# Due_Breakout_Board_Headers.net
KiCad netlist of a schematic drawn in Altium Designer
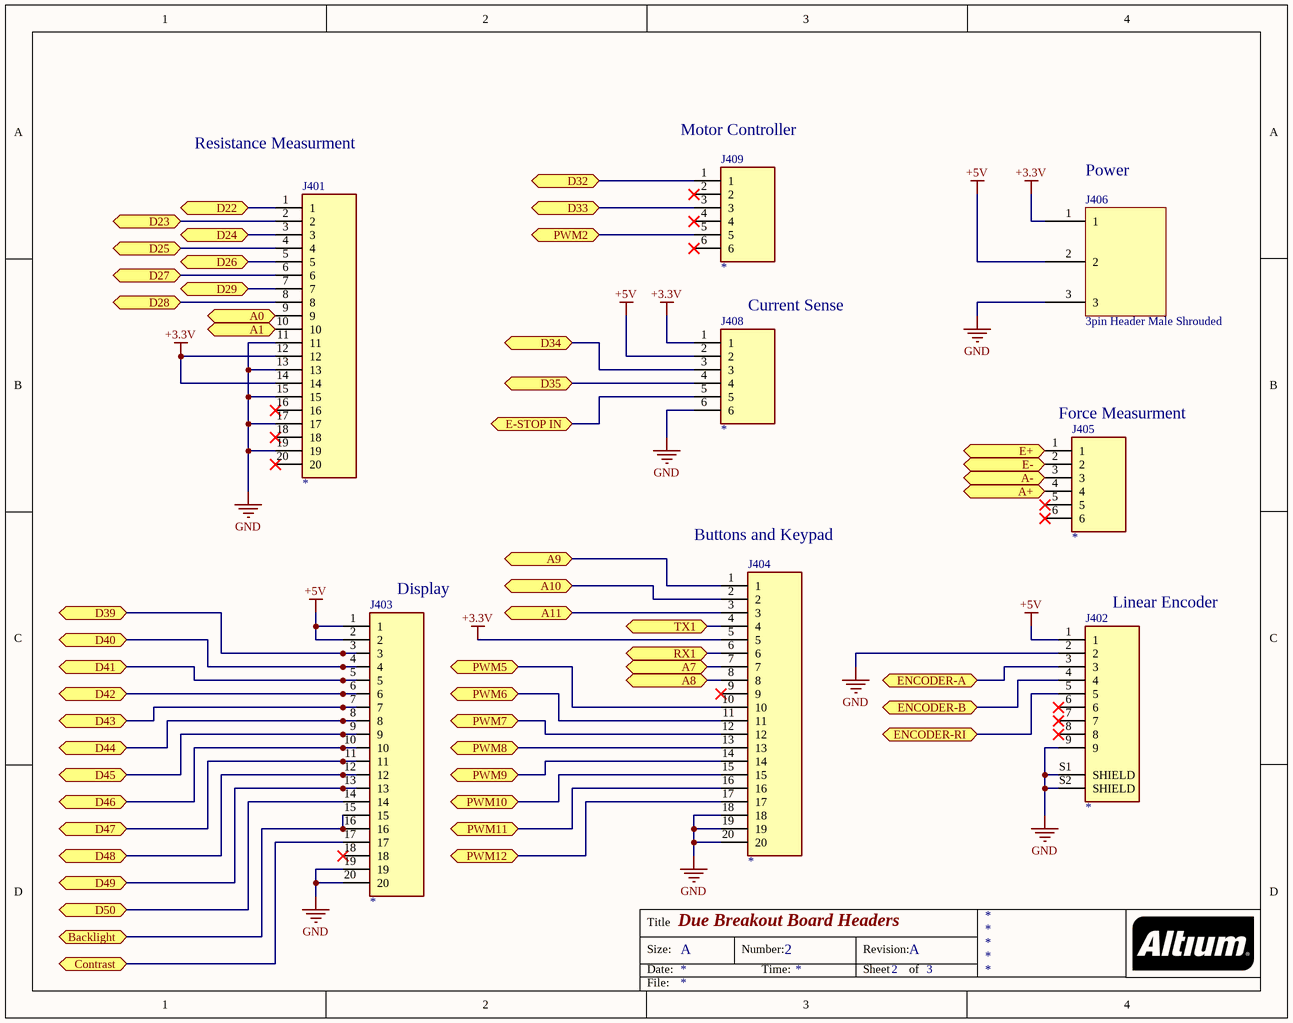
[diagram p0: Due_Breakout_Board Headers.SchDoc]

(export (version "E")
  (design (tool "Eeschema 10.0.6"))
  (components
    (comp (ref "J401")
      (value "*")
      (footprint "TE_1761681-7")
      (description "IDC LOW PRO HDR 50P VERT HT BLACK")
      (fields (field (name "MP") "1761681-7"))
      (libsource (lib "1761681-7") (part "1761681-7"))
    )
    (comp (ref "J402")
      (value "1-5747150-6")
      (footprint "TE_1-5747150-6")
      (description "9 Position D-Sub Receptacle, Female Sockets Connector")
      (fields (field (name "MF") "TE Connectivity") (field (name "COMMENT_1") "*"))
      (libsource (lib "1-5747150-6") (part "1-5747150-6"))
    )
    (comp (ref "J403")
      (value "*")
      (footprint "TE_1761681-7")
      (description "IDC LOW PRO HDR 50P VERT HT BLACK")
      (fields (field (name "MP") "1761681-7"))
      (libsource (lib "1761681-7") (part "1761681-7"))
    )
    (comp (ref "J404")
      (value "*")
      (footprint "TE_1761681-7")
      (description "IDC LOW PRO HDR 50P VERT HT BLACK")
      (fields (field (name "MP") "1761681-7"))
      (libsource (lib "1761681-7") (part "1761681-7"))
    )
    (comp (ref "J405")
      (value "*")
      (footprint "TE_1761681-1")
      (fields (field (name "MP") "1761681-1") (field (name "MF") "{'manufacturer': 'TE Connectivity'}"))
      (libsource (lib "1761681-1") (part "1761681-1"))
    )
    (comp (ref "J406")
      (value "3pin Header Male Shrouded")
      (footprint "3Pin Header")
      (libsource (lib "Components") (part "3pin Header Male Shrouded"))
    )
    (comp (ref "J408")
      (value "*")
      (footprint "TE_1761681-1")
      (fields (field (name "MP") "1761681-1") (field (name "MF") "{'manufacturer': 'TE Connectivity'}"))
      (libsource (lib "1761681-1") (part "1761681-1"))
    )
    (comp (ref "J409")
      (value "*")
      (footprint "TE_1761681-1")
      (fields (field (name "MP") "1761681-1") (field (name "MF") "{'manufacturer': 'TE Connectivity'}"))
      (libsource (lib "1761681-1") (part "1761681-1"))
    )
  )
  (nets
    (net (code "1") (name "+3.3V") (class "Default")
      (node (ref "J401") (pin "12") (pinfunction "12_12") (pintype "passive"))
      (node (ref "J401") (pin "14") (pinfunction "14_14") (pintype "passive"))
      (node (ref "J404") (pin "5") (pinfunction "5_5") (pintype "passive"))
      (node (ref "J406") (pin "1") (pinfunction "1_1") (pintype "passive"))
      (node (ref "J408") (pin "1") (pinfunction "1_1") (pintype "passive"))
    )
    (net (code "2") (name "+5V") (class "Default")
      (node (ref "J402") (pin "1") (pinfunction "1_1") (pintype "passive"))
      (node (ref "J403") (pin "1") (pinfunction "1_1") (pintype "passive"))
      (node (ref "J403") (pin "2") (pinfunction "2_2") (pintype "passive"))
      (node (ref "J406") (pin "2") (pinfunction "2_2") (pintype "passive"))
      (node (ref "J408") (pin "2") (pinfunction "2_2") (pintype "passive"))
    )
    (net (code "3") (name "/A+") (class "Default")
      (node (ref "J405") (pin "4") (pinfunction "4_4") (pintype "passive"))
    )
    (net (code "4") (name "/A-") (class "Default")
      (node (ref "J405") (pin "3") (pinfunction "3_3") (pintype "passive"))
    )
    (net (code "5") (name "/A0") (class "Default")
      (node (ref "J401") (pin "9") (pinfunction "9_9") (pintype "passive"))
    )
    (net (code "6") (name "/A1") (class "Default")
      (node (ref "J401") (pin "10") (pinfunction "10_10") (pintype "passive"))
    )
    (net (code "7") (name "/A7") (class "Default")
      (node (ref "J404") (pin "7") (pinfunction "7_7") (pintype "passive"))
    )
    (net (code "8") (name "/A8") (class "Default")
      (node (ref "J404") (pin "8") (pinfunction "8_8") (pintype "passive"))
    )
    (net (code "9") (name "/A9") (class "Default")
      (node (ref "J404") (pin "1") (pinfunction "1_1") (pintype "passive"))
    )
    (net (code "10") (name "/A10") (class "Default")
      (node (ref "J404") (pin "2") (pinfunction "2_2") (pintype "passive"))
    )
    (net (code "11") (name "/A11") (class "Default")
      (node (ref "J404") (pin "3") (pinfunction "3_3") (pintype "passive"))
    )
    (net (code "12") (name "/Backlight") (class "Default")
      (node (ref "J403") (pin "15") (pinfunction "15_15") (pintype "passive"))
      (node (ref "J403") (pin "16") (pinfunction "16_16") (pintype "passive"))
    )
    (net (code "13") (name "/Contrast") (class "Default")
      (node (ref "J403") (pin "17") (pinfunction "17_17") (pintype "passive"))
    )
    (net (code "14") (name "/D22") (class "Default")
      (node (ref "J401") (pin "1") (pinfunction "1_1") (pintype "passive"))
    )
    (net (code "15") (name "/D23") (class "Default")
      (node (ref "J401") (pin "2") (pinfunction "2_2") (pintype "passive"))
    )
    (net (code "16") (name "/D24") (class "Default")
      (node (ref "J401") (pin "3") (pinfunction "3_3") (pintype "passive"))
    )
    (net (code "17") (name "/D25") (class "Default")
      (node (ref "J401") (pin "4") (pinfunction "4_4") (pintype "passive"))
    )
    (net (code "18") (name "/D26") (class "Default")
      (node (ref "J401") (pin "5") (pinfunction "5_5") (pintype "passive"))
    )
    (net (code "19") (name "/D27") (class "Default")
      (node (ref "J401") (pin "6") (pinfunction "6_6") (pintype "passive"))
    )
    (net (code "20") (name "/D28") (class "Default")
      (node (ref "J401") (pin "8") (pinfunction "8_8") (pintype "passive"))
    )
    (net (code "21") (name "/D29") (class "Default")
      (node (ref "J401") (pin "7") (pinfunction "7_7") (pintype "passive"))
    )
    (net (code "22") (name "/D32") (class "Default")
      (node (ref "J409") (pin "1") (pinfunction "1_1") (pintype "passive"))
    )
    (net (code "23") (name "/D33") (class "Default")
      (node (ref "J409") (pin "3") (pinfunction "3_3") (pintype "passive"))
    )
    (net (code "24") (name "/D34") (class "Default")
      (node (ref "J408") (pin "3") (pinfunction "3_3") (pintype "passive"))
    )
    (net (code "25") (name "/D35") (class "Default")
      (node (ref "J408") (pin "4") (pinfunction "4_4") (pintype "passive"))
    )
    (net (code "26") (name "/D39") (class "Default")
      (node (ref "J403") (pin "3") (pinfunction "3_3") (pintype "passive"))
    )
    (net (code "27") (name "/D40") (class "Default")
      (node (ref "J403") (pin "4") (pinfunction "4_4") (pintype "passive"))
    )
    (net (code "28") (name "/D41") (class "Default")
      (node (ref "J403") (pin "5") (pinfunction "5_5") (pintype "passive"))
    )
    (net (code "29") (name "/D42") (class "Default")
      (node (ref "J403") (pin "6") (pinfunction "6_6") (pintype "passive"))
    )
    (net (code "30") (name "/D43") (class "Default")
      (node (ref "J403") (pin "7") (pinfunction "7_7") (pintype "passive"))
    )
    (net (code "31") (name "/D44") (class "Default")
      (node (ref "J403") (pin "8") (pinfunction "8_8") (pintype "passive"))
    )
    (net (code "32") (name "/D45") (class "Default")
      (node (ref "J403") (pin "9") (pinfunction "9_9") (pintype "passive"))
    )
    (net (code "33") (name "/D46") (class "Default")
      (node (ref "J403") (pin "10") (pinfunction "10_10") (pintype "passive"))
    )
    (net (code "34") (name "/D47") (class "Default")
      (node (ref "J403") (pin "11") (pinfunction "11_11") (pintype "passive"))
    )
    (net (code "35") (name "/D48") (class "Default")
      (node (ref "J403") (pin "12") (pinfunction "12_12") (pintype "passive"))
    )
    (net (code "36") (name "/D49") (class "Default")
      (node (ref "J403") (pin "13") (pinfunction "13_13") (pintype "passive"))
    )
    (net (code "37") (name "/D50") (class "Default")
      (node (ref "J403") (pin "14") (pinfunction "14_14") (pintype "passive"))
    )
    (net (code "38") (name "/E+") (class "Default")
      (node (ref "J405") (pin "1") (pinfunction "1_1") (pintype "passive"))
    )
    (net (code "39") (name "/E-") (class "Default")
      (node (ref "J405") (pin "2") (pinfunction "2_2") (pintype "passive"))
    )
    (net (code "40") (name "/E-STOP IN") (class "Default")
      (node (ref "J408") (pin "5") (pinfunction "5_5") (pintype "passive"))
    )
    (net (code "41") (name "/ENCODER-A") (class "Default")
      (node (ref "J402") (pin "3") (pinfunction "3_3") (pintype "passive"))
    )
    (net (code "42") (name "/ENCODER-B") (class "Default")
      (node (ref "J402") (pin "4") (pinfunction "4_4") (pintype "passive"))
    )
    (net (code "43") (name "/ENCODER-RI") (class "Default")
      (node (ref "J402") (pin "5") (pinfunction "5_5") (pintype "passive"))
    )
    (net (code "44") (name "/PWM2") (class "Default")
      (node (ref "J409") (pin "5") (pinfunction "5_5") (pintype "passive"))
    )
    (net (code "45") (name "/PWM5") (class "Default")
      (node (ref "J404") (pin "10") (pinfunction "10_10") (pintype "passive"))
    )
    (net (code "46") (name "/PWM6") (class "Default")
      (node (ref "J404") (pin "11") (pinfunction "11_11") (pintype "passive"))
    )
    (net (code "47") (name "/PWM7") (class "Default")
      (node (ref "J404") (pin "12") (pinfunction "12_12") (pintype "passive"))
    )
    (net (code "48") (name "/PWM8") (class "Default")
      (node (ref "J404") (pin "13") (pinfunction "13_13") (pintype "passive"))
    )
    (net (code "49") (name "/PWM9") (class "Default")
      (node (ref "J404") (pin "14") (pinfunction "14_14") (pintype "passive"))
    )
    (net (code "50") (name "/PWM10") (class "Default")
      (node (ref "J404") (pin "15") (pinfunction "15_15") (pintype "passive"))
    )
    (net (code "51") (name "/PWM11") (class "Default")
      (node (ref "J404") (pin "16") (pinfunction "16_16") (pintype "passive"))
    )
    (net (code "52") (name "/PWM12") (class "Default")
      (node (ref "J404") (pin "17") (pinfunction "17_17") (pintype "passive"))
    )
    (net (code "53") (name "/RX1") (class "Default")
      (node (ref "J404") (pin "6") (pinfunction "6_6") (pintype "passive"))
    )
    (net (code "54") (name "/TX1") (class "Default")
      (node (ref "J404") (pin "4") (pinfunction "4_4") (pintype "passive"))
    )
    (net (code "55") (name "GND") (class "Default")
      (node (ref "J401") (pin "11") (pinfunction "11_11") (pintype "passive"))
      (node (ref "J401") (pin "13") (pinfunction "13_13") (pintype "passive"))
      (node (ref "J401") (pin "15") (pinfunction "15_15") (pintype "passive"))
      (node (ref "J401") (pin "17") (pinfunction "17_17") (pintype "passive"))
      (node (ref "J401") (pin "19") (pinfunction "19_19") (pintype "passive"))
      (node (ref "J402") (pin "2") (pinfunction "2_2") (pintype "passive"))
      (node (ref "J402") (pin "9") (pinfunction "9_9") (pintype "passive"))
      (node (ref "J402") (pin "S1") (pinfunction "SHIELD_S1") (pintype "passive"))
      (node (ref "J402") (pin "S2") (pinfunction "SHIELD_S2") (pintype "passive"))
      (node (ref "J403") (pin "19") (pinfunction "19_19") (pintype "passive"))
      (node (ref "J403") (pin "20") (pinfunction "20_20") (pintype "passive"))
      (node (ref "J404") (pin "18") (pinfunction "18_18") (pintype "passive"))
      (node (ref "J404") (pin "19") (pinfunction "19_19") (pintype "passive"))
      (node (ref "J404") (pin "20") (pinfunction "20_20") (pintype "passive"))
      (node (ref "J406") (pin "3") (pinfunction "3_3") (pintype "passive"))
      (node (ref "J408") (pin "6") (pinfunction "6_6") (pintype "passive"))
    )
    (net (code "56") (name "unconnected-(J401-Pad16)") (class "Default")
      (node (ref "J401") (pin "16") (pinfunction "16_16") (pintype "passive+no_connect"))
    )
    (net (code "57") (name "unconnected-(J401-Pad18)") (class "Default")
      (node (ref "J401") (pin "18") (pinfunction "18_18") (pintype "passive+no_connect"))
    )
    (net (code "58") (name "unconnected-(J401-Pad20)") (class "Default")
      (node (ref "J401") (pin "20") (pinfunction "20_20") (pintype "passive+no_connect"))
    )
    (net (code "59") (name "unconnected-(J402-Pad6)") (class "Default")
      (node (ref "J402") (pin "6") (pinfunction "6_6") (pintype "passive+no_connect"))
    )
    (net (code "60") (name "unconnected-(J402-Pad7)") (class "Default")
      (node (ref "J402") (pin "7") (pinfunction "7_7") (pintype "passive+no_connect"))
    )
    (net (code "61") (name "unconnected-(J402-Pad8)") (class "Default")
      (node (ref "J402") (pin "8") (pinfunction "8_8") (pintype "passive+no_connect"))
    )
    (net (code "62") (name "unconnected-(J403-Pad18)") (class "Default")
      (node (ref "J403") (pin "18") (pinfunction "18_18") (pintype "passive+no_connect"))
    )
    (net (code "63") (name "unconnected-(J404-Pad9)") (class "Default")
      (node (ref "J404") (pin "9") (pinfunction "9_9") (pintype "passive+no_connect"))
    )
    (net (code "64") (name "unconnected-(J405-Pad5)") (class "Default")
      (node (ref "J405") (pin "5") (pinfunction "5_5") (pintype "passive+no_connect"))
    )
    (net (code "65") (name "unconnected-(J405-Pad6)") (class "Default")
      (node (ref "J405") (pin "6") (pinfunction "6_6") (pintype "passive+no_connect"))
    )
    (net (code "66") (name "unconnected-(J409-Pad2)") (class "Default")
      (node (ref "J409") (pin "2") (pinfunction "2_2") (pintype "passive+no_connect"))
    )
    (net (code "67") (name "unconnected-(J409-Pad4)") (class "Default")
      (node (ref "J409") (pin "4") (pinfunction "4_4") (pintype "passive+no_connect"))
    )
    (net (code "68") (name "unconnected-(J409-Pad6)") (class "Default")
      (node (ref "J409") (pin "6") (pinfunction "6_6") (pintype "passive+no_connect"))
    )
  )
)
